# ProdTest.net
KiCad netlist of a schematic drawn in EAGLE
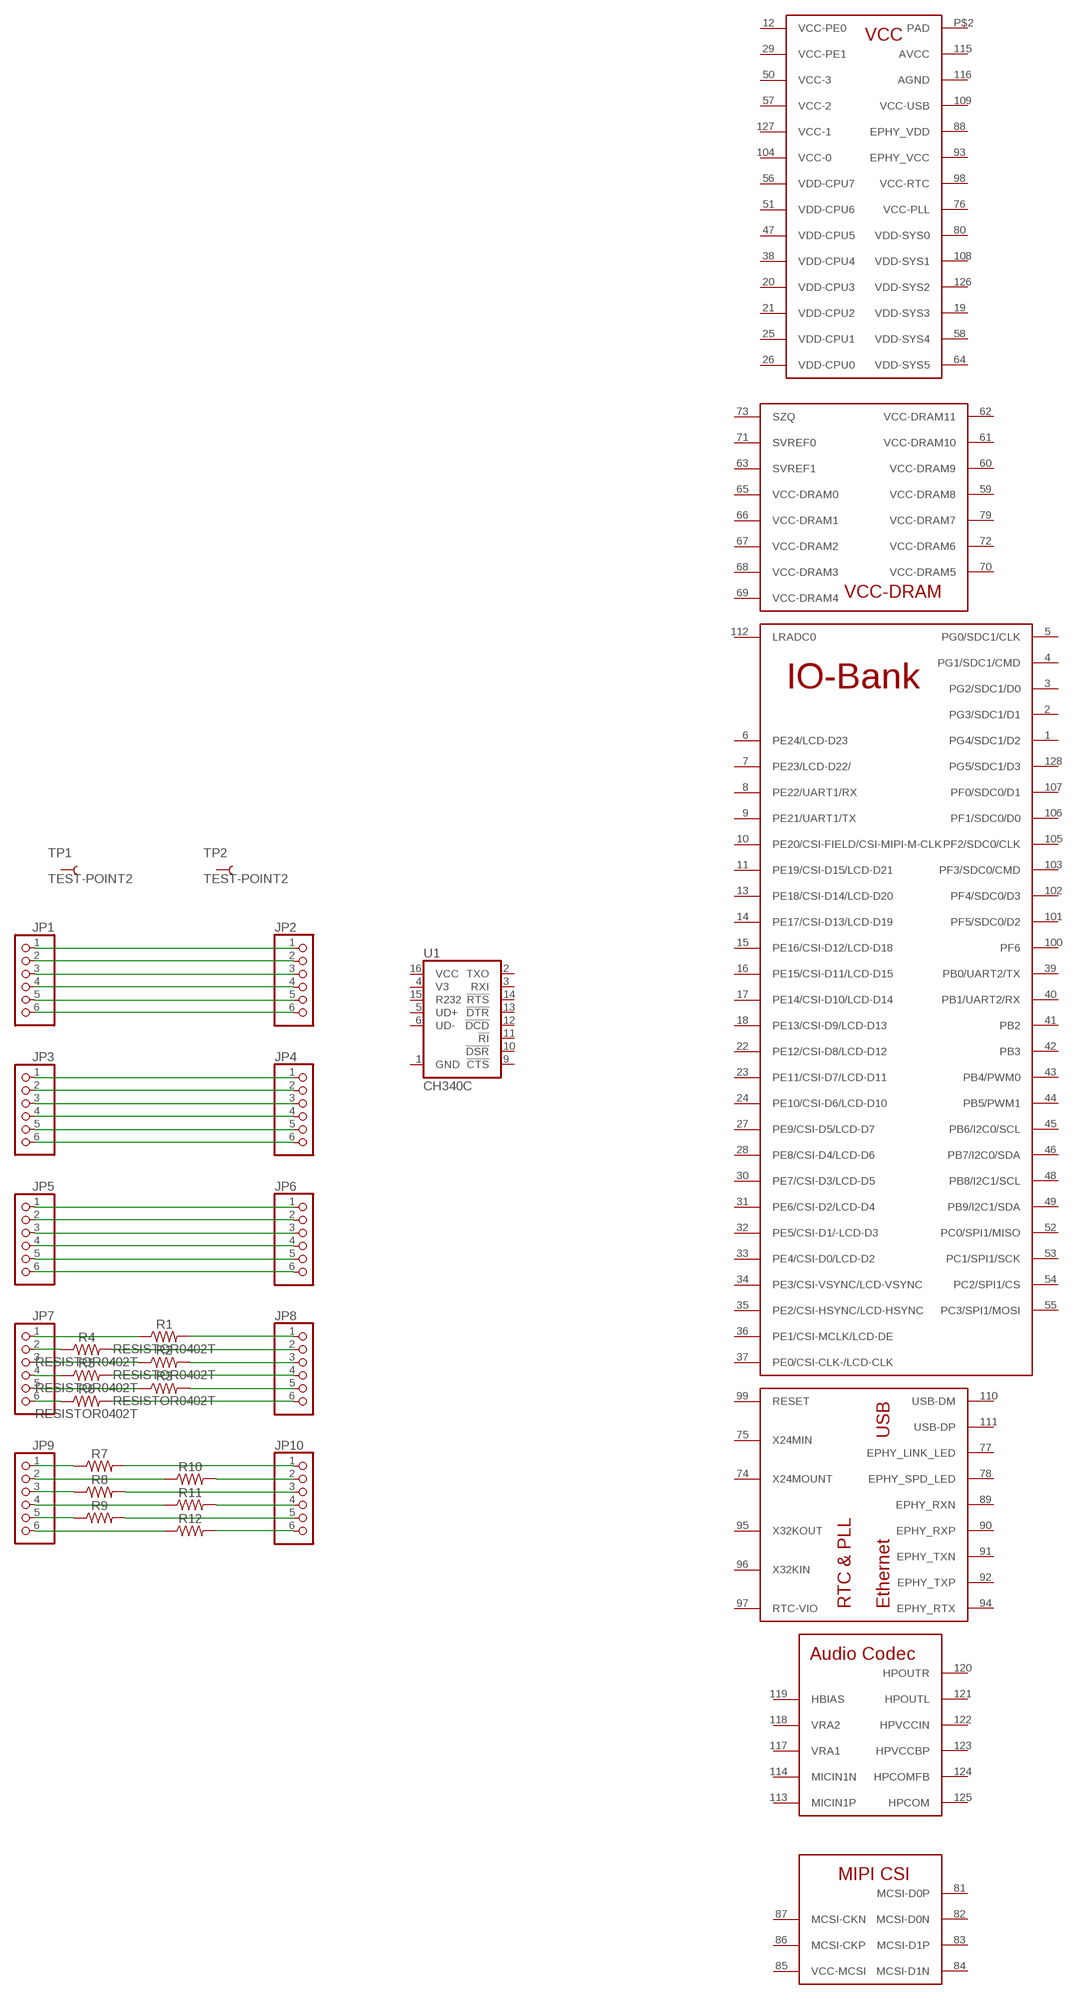
[diagram p0: schematic, sheet 1]

(export (version "E")
  (design (tool "Eeschema 10.0.6"))
  (components
    (comp (ref "JP1")
      (value "PINHD-1X6")
      (footprint "eagle-import:1X06")
      (libsource (lib "eagle-import") (part "PINHD-1X6"))
    )
    (comp (ref "JP2")
      (value "PINHD-1X6")
      (footprint "eagle-import:1X06")
      (libsource (lib "eagle-import") (part "PINHD-1X6"))
    )
    (comp (ref "JP3")
      (value "PINHD-1X6")
      (footprint "eagle-import:1X06")
      (libsource (lib "eagle-import") (part "PINHD-1X6"))
    )
    (comp (ref "JP4")
      (value "PINHD-1X6")
      (footprint "eagle-import:1X06")
      (libsource (lib "eagle-import") (part "PINHD-1X6"))
    )
    (comp (ref "JP5")
      (value "PINHD-1X6")
      (footprint "eagle-import:1X06")
      (libsource (lib "eagle-import") (part "PINHD-1X6"))
    )
    (comp (ref "JP6")
      (value "PINHD-1X6")
      (footprint "eagle-import:1X06")
      (libsource (lib "eagle-import") (part "PINHD-1X6"))
    )
    (comp (ref "JP7")
      (value "PINHD-1X6")
      (footprint "eagle-import:1X06")
      (libsource (lib "eagle-import") (part "PINHD-1X6"))
    )
    (comp (ref "JP8")
      (value "PINHD-1X6")
      (footprint "eagle-import:1X06")
      (libsource (lib "eagle-import") (part "PINHD-1X6"))
    )
    (comp (ref "JP9")
      (value "PINHD-1X6")
      (footprint "eagle-import:1X06")
      (libsource (lib "eagle-import") (part "PINHD-1X6"))
    )
    (comp (ref "JP10")
      (value "PINHD-1X6")
      (footprint "eagle-import:1X06")
      (libsource (lib "eagle-import") (part "PINHD-1X6"))
    )
    (comp (ref "R1")
      (value "RESISTOR0402T")
      (footprint "eagle-import:0402-TIGHT")
      (libsource (lib "eagle-import") (part "RESISTOR0402T"))
    )
    (comp (ref "R2")
      (value "RESISTOR0402T")
      (footprint "eagle-import:0402-TIGHT")
      (libsource (lib "eagle-import") (part "RESISTOR0402T"))
    )
    (comp (ref "R3")
      (value "RESISTOR0402T")
      (footprint "eagle-import:0402-TIGHT")
      (libsource (lib "eagle-import") (part "RESISTOR0402T"))
    )
    (comp (ref "R4")
      (value "RESISTOR0402T")
      (footprint "eagle-import:0402-TIGHT")
      (libsource (lib "eagle-import") (part "RESISTOR0402T"))
    )
    (comp (ref "R5")
      (value "RESISTOR0402T")
      (footprint "eagle-import:0402-TIGHT")
      (libsource (lib "eagle-import") (part "RESISTOR0402T"))
    )
    (comp (ref "R6")
      (value "RESISTOR0402T")
      (footprint "eagle-import:0402-TIGHT")
      (libsource (lib "eagle-import") (part "RESISTOR0402T"))
    )
    (comp (ref "R7")
      (value "RESISTOR0603")
      (footprint "eagle-import:0603")
      (libsource (lib "eagle-import") (part "RESISTOR0603"))
    )
    (comp (ref "R8")
      (value "RESISTOR0603")
      (footprint "eagle-import:0603")
      (libsource (lib "eagle-import") (part "RESISTOR0603"))
    )
    (comp (ref "R9")
      (value "RESISTOR0603")
      (footprint "eagle-import:0603")
      (libsource (lib "eagle-import") (part "RESISTOR0603"))
    )
    (comp (ref "R10")
      (value "RESISTOR0603")
      (footprint "eagle-import:0603")
      (libsource (lib "eagle-import") (part "RESISTOR0603"))
    )
    (comp (ref "R11")
      (value "RESISTOR0603")
      (footprint "eagle-import:0603")
      (libsource (lib "eagle-import") (part "RESISTOR0603"))
    )
    (comp (ref "R12")
      (value "RESISTOR0603")
      (footprint "eagle-import:0603")
      (libsource (lib "eagle-import") (part "RESISTOR0603"))
    )
    (comp (ref "TP1")
      (value "TEST-POINT2")
      (footprint "eagle-import:PAD.02X.02")
      (libsource (lib "eagle-import") (part "TEST-POINT2"))
    )
    (comp (ref "TP2")
      (value "TEST-POINT2")
      (footprint "eagle-import:PAD.02X.02")
      (libsource (lib "eagle-import") (part "TEST-POINT2"))
    )
    (comp (ref "U$1")
      (value "V3S")
      (footprint "eagle-import:QFP-128")
      (libsource (lib "eagle-import") (part "V3S"))
    )
    (comp (ref "U1")
      (value "CH340C")
      (footprint "eagle-import:SO016")
      (libsource (lib "eagle-import") (part "CH340C"))
    )
  )
  (nets
    (net (code "1") (name "Net-(JP1-Pad1)") (class "Default")
      (node (ref "JP1") (pin "1") (pinfunction "1_1") (pintype "passive"))
      (node (ref "JP2") (pin "1") (pinfunction "1_1") (pintype "passive"))
    )
    (net (code "2") (name "Net-(JP1-Pad2)") (class "Default")
      (node (ref "JP1") (pin "2") (pinfunction "2_2") (pintype "passive"))
      (node (ref "JP2") (pin "2") (pinfunction "2_2") (pintype "passive"))
    )
    (net (code "3") (name "Net-(JP1-Pad3)") (class "Default")
      (node (ref "JP1") (pin "3") (pinfunction "3_3") (pintype "passive"))
      (node (ref "JP2") (pin "3") (pinfunction "3_3") (pintype "passive"))
    )
    (net (code "4") (name "Net-(JP1-Pad4)") (class "Default")
      (node (ref "JP1") (pin "4") (pinfunction "4_4") (pintype "passive"))
      (node (ref "JP2") (pin "4") (pinfunction "4_4") (pintype "passive"))
    )
    (net (code "5") (name "Net-(JP1-Pad5)") (class "Default")
      (node (ref "JP1") (pin "5") (pinfunction "5_5") (pintype "passive"))
      (node (ref "JP2") (pin "5") (pinfunction "5_5") (pintype "passive"))
    )
    (net (code "6") (name "Net-(JP1-Pad6)") (class "Default")
      (node (ref "JP1") (pin "6") (pinfunction "6_6") (pintype "passive"))
      (node (ref "JP2") (pin "6") (pinfunction "6_6") (pintype "passive"))
    )
    (net (code "7") (name "Net-(JP3-Pad1)") (class "Default")
      (node (ref "JP3") (pin "1") (pinfunction "1_1") (pintype "passive"))
      (node (ref "JP4") (pin "1") (pinfunction "1_1") (pintype "passive"))
    )
    (net (code "8") (name "Net-(JP3-Pad2)") (class "Default")
      (node (ref "JP3") (pin "2") (pinfunction "2_2") (pintype "passive"))
      (node (ref "JP4") (pin "2") (pinfunction "2_2") (pintype "passive"))
    )
    (net (code "9") (name "Net-(JP3-Pad3)") (class "Default")
      (node (ref "JP3") (pin "3") (pinfunction "3_3") (pintype "passive"))
      (node (ref "JP4") (pin "3") (pinfunction "3_3") (pintype "passive"))
    )
    (net (code "10") (name "Net-(JP3-Pad4)") (class "Default")
      (node (ref "JP3") (pin "4") (pinfunction "4_4") (pintype "passive"))
      (node (ref "JP4") (pin "4") (pinfunction "4_4") (pintype "passive"))
    )
    (net (code "11") (name "Net-(JP3-Pad5)") (class "Default")
      (node (ref "JP3") (pin "5") (pinfunction "5_5") (pintype "passive"))
      (node (ref "JP4") (pin "5") (pinfunction "5_5") (pintype "passive"))
    )
    (net (code "12") (name "Net-(JP3-Pad6)") (class "Default")
      (node (ref "JP3") (pin "6") (pinfunction "6_6") (pintype "passive"))
      (node (ref "JP4") (pin "6") (pinfunction "6_6") (pintype "passive"))
    )
    (net (code "13") (name "Net-(JP5-Pad1)") (class "Default")
      (node (ref "JP5") (pin "1") (pinfunction "1_1") (pintype "passive"))
      (node (ref "JP6") (pin "1") (pinfunction "1_1") (pintype "passive"))
    )
    (net (code "14") (name "Net-(JP5-Pad2)") (class "Default")
      (node (ref "JP5") (pin "2") (pinfunction "2_2") (pintype "passive"))
      (node (ref "JP6") (pin "2") (pinfunction "2_2") (pintype "passive"))
    )
    (net (code "15") (name "Net-(JP5-Pad3)") (class "Default")
      (node (ref "JP5") (pin "3") (pinfunction "3_3") (pintype "passive"))
      (node (ref "JP6") (pin "3") (pinfunction "3_3") (pintype "passive"))
    )
    (net (code "16") (name "Net-(JP5-Pad4)") (class "Default")
      (node (ref "JP5") (pin "4") (pinfunction "4_4") (pintype "passive"))
      (node (ref "JP6") (pin "4") (pinfunction "4_4") (pintype "passive"))
    )
    (net (code "17") (name "Net-(JP5-Pad5)") (class "Default")
      (node (ref "JP5") (pin "5") (pinfunction "5_5") (pintype "passive"))
      (node (ref "JP6") (pin "5") (pinfunction "5_5") (pintype "passive"))
    )
    (net (code "18") (name "Net-(JP5-Pad6)") (class "Default")
      (node (ref "JP5") (pin "6") (pinfunction "6_6") (pintype "passive"))
      (node (ref "JP6") (pin "6") (pinfunction "6_6") (pintype "passive"))
    )
    (net (code "19") (name "Net-(JP7-Pad1)") (class "Default")
      (node (ref "JP7") (pin "1") (pinfunction "1_1") (pintype "passive"))
      (node (ref "R1") (pin "1") (pinfunction "1_1") (pintype "passive"))
    )
    (net (code "20") (name "Net-(JP7-Pad2)") (class "Default")
      (node (ref "JP7") (pin "2") (pinfunction "2_2") (pintype "passive"))
      (node (ref "R4") (pin "1") (pinfunction "1_1") (pintype "passive"))
    )
    (net (code "21") (name "Net-(JP7-Pad3)") (class "Default")
      (node (ref "JP7") (pin "3") (pinfunction "3_3") (pintype "passive"))
      (node (ref "R2") (pin "1") (pinfunction "1_1") (pintype "passive"))
    )
    (net (code "22") (name "Net-(JP7-Pad4)") (class "Default")
      (node (ref "JP7") (pin "4") (pinfunction "4_4") (pintype "passive"))
      (node (ref "R5") (pin "1") (pinfunction "1_1") (pintype "passive"))
    )
    (net (code "23") (name "Net-(JP7-Pad5)") (class "Default")
      (node (ref "JP7") (pin "5") (pinfunction "5_5") (pintype "passive"))
      (node (ref "R3") (pin "1") (pinfunction "1_1") (pintype "passive"))
    )
    (net (code "24") (name "Net-(JP7-Pad6)") (class "Default")
      (node (ref "JP7") (pin "6") (pinfunction "6_6") (pintype "passive"))
      (node (ref "R6") (pin "1") (pinfunction "1_1") (pintype "passive"))
    )
    (net (code "25") (name "Net-(JP8-Pad1)") (class "Default")
      (node (ref "JP8") (pin "1") (pinfunction "1_1") (pintype "passive"))
      (node (ref "R1") (pin "2") (pinfunction "2_2") (pintype "passive"))
    )
    (net (code "26") (name "Net-(JP8-Pad2)") (class "Default")
      (node (ref "JP8") (pin "2") (pinfunction "2_2") (pintype "passive"))
      (node (ref "R4") (pin "2") (pinfunction "2_2") (pintype "passive"))
    )
    (net (code "27") (name "Net-(JP8-Pad3)") (class "Default")
      (node (ref "JP8") (pin "3") (pinfunction "3_3") (pintype "passive"))
      (node (ref "R2") (pin "2") (pinfunction "2_2") (pintype "passive"))
    )
    (net (code "28") (name "Net-(JP8-Pad4)") (class "Default")
      (node (ref "JP8") (pin "4") (pinfunction "4_4") (pintype "passive"))
      (node (ref "R5") (pin "2") (pinfunction "2_2") (pintype "passive"))
    )
    (net (code "29") (name "Net-(JP8-Pad5)") (class "Default")
      (node (ref "JP8") (pin "5") (pinfunction "5_5") (pintype "passive"))
      (node (ref "R3") (pin "2") (pinfunction "2_2") (pintype "passive"))
    )
    (net (code "30") (name "Net-(JP8-Pad6)") (class "Default")
      (node (ref "JP8") (pin "6") (pinfunction "6_6") (pintype "passive"))
      (node (ref "R6") (pin "2") (pinfunction "2_2") (pintype "passive"))
    )
    (net (code "31") (name "Net-(JP9-Pad1)") (class "Default")
      (node (ref "JP9") (pin "1") (pinfunction "1_1") (pintype "passive"))
      (node (ref "R7") (pin "1") (pinfunction "1_1") (pintype "passive"))
    )
    (net (code "32") (name "Net-(JP9-Pad2)") (class "Default")
      (node (ref "JP9") (pin "2") (pinfunction "2_2") (pintype "passive"))
      (node (ref "R10") (pin "1") (pinfunction "1_1") (pintype "passive"))
    )
    (net (code "33") (name "Net-(JP9-Pad3)") (class "Default")
      (node (ref "JP9") (pin "3") (pinfunction "3_3") (pintype "passive"))
      (node (ref "R8") (pin "1") (pinfunction "1_1") (pintype "passive"))
    )
    (net (code "34") (name "Net-(JP9-Pad4)") (class "Default")
      (node (ref "JP9") (pin "4") (pinfunction "4_4") (pintype "passive"))
      (node (ref "R11") (pin "1") (pinfunction "1_1") (pintype "passive"))
    )
    (net (code "35") (name "Net-(JP9-Pad5)") (class "Default")
      (node (ref "JP9") (pin "5") (pinfunction "5_5") (pintype "passive"))
      (node (ref "R9") (pin "1") (pinfunction "1_1") (pintype "passive"))
    )
    (net (code "36") (name "Net-(JP9-Pad6)") (class "Default")
      (node (ref "JP9") (pin "6") (pinfunction "6_6") (pintype "passive"))
      (node (ref "R12") (pin "1") (pinfunction "1_1") (pintype "passive"))
    )
    (net (code "37") (name "Net-(JP10-Pad1)") (class "Default")
      (node (ref "JP10") (pin "1") (pinfunction "1_1") (pintype "passive"))
      (node (ref "R7") (pin "2") (pinfunction "2_2") (pintype "passive"))
    )
    (net (code "38") (name "Net-(JP10-Pad2)") (class "Default")
      (node (ref "JP10") (pin "2") (pinfunction "2_2") (pintype "passive"))
      (node (ref "R10") (pin "2") (pinfunction "2_2") (pintype "passive"))
    )
    (net (code "39") (name "Net-(JP10-Pad3)") (class "Default")
      (node (ref "JP10") (pin "3") (pinfunction "3_3") (pintype "passive"))
      (node (ref "R8") (pin "2") (pinfunction "2_2") (pintype "passive"))
    )
    (net (code "40") (name "Net-(JP10-Pad4)") (class "Default")
      (node (ref "JP10") (pin "4") (pinfunction "4_4") (pintype "passive"))
      (node (ref "R11") (pin "2") (pinfunction "2_2") (pintype "passive"))
    )
    (net (code "41") (name "Net-(JP10-Pad5)") (class "Default")
      (node (ref "JP10") (pin "5") (pinfunction "5_5") (pintype "passive"))
      (node (ref "R9") (pin "2") (pinfunction "2_2") (pintype "passive"))
    )
    (net (code "42") (name "Net-(JP10-Pad6)") (class "Default")
      (node (ref "JP10") (pin "6") (pinfunction "6_6") (pintype "passive"))
      (node (ref "R12") (pin "2") (pinfunction "2_2") (pintype "passive"))
    )
    (net (code "43") (name "unconnected-(TP1-Pad1)") (class "Default")
      (node (ref "TP1") (pin "1") (pinfunction "1_1") (pintype "bidirectional"))
    )
    (net (code "44") (name "unconnected-(TP2-Pad1)") (class "Default")
      (node (ref "TP2") (pin "1") (pinfunction "1_1") (pintype "bidirectional"))
    )
    (net (code "45") (name "unconnected-(U$1-AGND-Pad116)") (class "Default")
      (node (ref "U$1") (pin "116") (pinfunction "AGND_116") (pintype "bidirectional"))
    )
    (net (code "46") (name "unconnected-(U$1-AVCC-Pad115)") (class "Default")
      (node (ref "U$1") (pin "115") (pinfunction "AVCC_115") (pintype "bidirectional"))
    )
    (net (code "47") (name "unconnected-(U$1-EPHY_LINK_LED-Pad77)") (class "Default")
      (node (ref "U$1") (pin "77") (pinfunction "EPHY_LINK_LED_77") (pintype "bidirectional"))
    )
    (net (code "48") (name "unconnected-(U$1-EPHY_RTX-Pad94)") (class "Default")
      (node (ref "U$1") (pin "94") (pinfunction "EPHY_RTX_94") (pintype "bidirectional"))
    )
    (net (code "49") (name "unconnected-(U$1-EPHY_RXN-Pad89)") (class "Default")
      (node (ref "U$1") (pin "89") (pinfunction "EPHY_RXN_89") (pintype "bidirectional"))
    )
    (net (code "50") (name "unconnected-(U$1-EPHY_RXP-Pad90)") (class "Default")
      (node (ref "U$1") (pin "90") (pinfunction "EPHY_RXP_90") (pintype "bidirectional"))
    )
    (net (code "51") (name "unconnected-(U$1-EPHY_SPD_LED-Pad78)") (class "Default")
      (node (ref "U$1") (pin "78") (pinfunction "EPHY_SPD_LED_78") (pintype "bidirectional"))
    )
    (net (code "52") (name "unconnected-(U$1-EPHY_TXN-Pad91)") (class "Default")
      (node (ref "U$1") (pin "91") (pinfunction "EPHY_TXN_91") (pintype "bidirectional"))
    )
    (net (code "53") (name "unconnected-(U$1-EPHY_TXP-Pad92)") (class "Default")
      (node (ref "U$1") (pin "92") (pinfunction "EPHY_TXP_92") (pintype "bidirectional"))
    )
    (net (code "54") (name "unconnected-(U$1-EPHY_VCC-Pad93)") (class "Default")
      (node (ref "U$1") (pin "93") (pinfunction "EPHY_VCC_93") (pintype "bidirectional"))
    )
    (net (code "55") (name "unconnected-(U$1-EPHY_VDD-Pad88)") (class "Default")
      (node (ref "U$1") (pin "88") (pinfunction "EPHY_VDD_88") (pintype "bidirectional"))
    )
    (net (code "56") (name "unconnected-(U$1-HBIAS-Pad119)") (class "Default")
      (node (ref "U$1") (pin "119") (pinfunction "HBIAS_119") (pintype "bidirectional"))
    )
    (net (code "57") (name "unconnected-(U$1-HPCOM-Pad125)") (class "Default")
      (node (ref "U$1") (pin "125") (pinfunction "HPCOM_125") (pintype "bidirectional"))
    )
    (net (code "58") (name "unconnected-(U$1-HPCOMFB-Pad124)") (class "Default")
      (node (ref "U$1") (pin "124") (pinfunction "HPCOMFB_124") (pintype "bidirectional"))
    )
    (net (code "59") (name "unconnected-(U$1-HPOUTL-Pad121)") (class "Default")
      (node (ref "U$1") (pin "121") (pinfunction "HPOUTL_121") (pintype "bidirectional"))
    )
    (net (code "60") (name "unconnected-(U$1-HPOUTR-Pad120)") (class "Default")
      (node (ref "U$1") (pin "120") (pinfunction "HPOUTR_120") (pintype "bidirectional"))
    )
    (net (code "61") (name "unconnected-(U$1-HPVCCBP-Pad123)") (class "Default")
      (node (ref "U$1") (pin "123") (pinfunction "HPVCCBP_123") (pintype "bidirectional"))
    )
    (net (code "62") (name "unconnected-(U$1-HPVCCIN-Pad122)") (class "Default")
      (node (ref "U$1") (pin "122") (pinfunction "HPVCCIN_122") (pintype "bidirectional"))
    )
    (net (code "63") (name "unconnected-(U$1-LRADC0-Pad112)") (class "Default")
      (node (ref "U$1") (pin "112") (pinfunction "LRADC0_112") (pintype "bidirectional"))
    )
    (net (code "64") (name "unconnected-(U$1-MCSI-CKN-Pad87)") (class "Default")
      (node (ref "U$1") (pin "87") (pinfunction "MCSI-CKN_87") (pintype "bidirectional"))
    )
    (net (code "65") (name "unconnected-(U$1-MCSI-CKP-Pad86)") (class "Default")
      (node (ref "U$1") (pin "86") (pinfunction "MCSI-CKP_86") (pintype "bidirectional"))
    )
    (net (code "66") (name "unconnected-(U$1-MCSI-D0N-Pad82)") (class "Default")
      (node (ref "U$1") (pin "82") (pinfunction "MCSI-D0N_82") (pintype "bidirectional"))
    )
    (net (code "67") (name "unconnected-(U$1-MCSI-D0P-Pad81)") (class "Default")
      (node (ref "U$1") (pin "81") (pinfunction "MCSI-D0P_81") (pintype "bidirectional"))
    )
    (net (code "68") (name "unconnected-(U$1-MCSI-D1N-Pad84)") (class "Default")
      (node (ref "U$1") (pin "84") (pinfunction "MCSI-D1N_84") (pintype "bidirectional"))
    )
    (net (code "69") (name "unconnected-(U$1-MCSI-D1P-Pad83)") (class "Default")
      (node (ref "U$1") (pin "83") (pinfunction "MCSI-D1P_83") (pintype "bidirectional"))
    )
    (net (code "70") (name "unconnected-(U$1-MICIN1N-Pad114)") (class "Default")
      (node (ref "U$1") (pin "114") (pinfunction "MICIN1N_114") (pintype "bidirectional"))
    )
    (net (code "71") (name "unconnected-(U$1-MICIN1P-Pad113)") (class "Default")
      (node (ref "U$1") (pin "113") (pinfunction "MICIN1P_113") (pintype "bidirectional"))
    )
    (net (code "72") (name "unconnected-(U$1-PAD-PadP$2)") (class "Default")
      (node (ref "U$1") (pin "P$2") (pinfunction "PAD_P$2") (pintype "bidirectional"))
    )
    (net (code "73") (name "unconnected-(U$1-PB0{slash}UART2{slash}TX-Pad39)") (class "Default")
      (node (ref "U$1") (pin "39") (pinfunction "PB0/UART2/TX_39") (pintype "bidirectional"))
    )
    (net (code "74") (name "unconnected-(U$1-PB1{slash}UART2{slash}RX-Pad40)") (class "Default")
      (node (ref "U$1") (pin "40") (pinfunction "PB1/UART2/RX_40") (pintype "bidirectional"))
    )
    (net (code "75") (name "unconnected-(U$1-PB2-Pad41)") (class "Default")
      (node (ref "U$1") (pin "41") (pinfunction "PB2_41") (pintype "bidirectional"))
    )
    (net (code "76") (name "unconnected-(U$1-PB3-Pad42)") (class "Default")
      (node (ref "U$1") (pin "42") (pinfunction "PB3_42") (pintype "bidirectional"))
    )
    (net (code "77") (name "unconnected-(U$1-PB4{slash}PWM0-Pad43)") (class "Default")
      (node (ref "U$1") (pin "43") (pinfunction "PB4/PWM0_43") (pintype "bidirectional"))
    )
    (net (code "78") (name "unconnected-(U$1-PB5{slash}PWM1-Pad44)") (class "Default")
      (node (ref "U$1") (pin "44") (pinfunction "PB5/PWM1_44") (pintype "bidirectional"))
    )
    (net (code "79") (name "unconnected-(U$1-PB6{slash}I2C0{slash}SCL-Pad45)") (class "Default")
      (node (ref "U$1") (pin "45") (pinfunction "PB6/I2C0/SCL_45") (pintype "bidirectional"))
    )
    (net (code "80") (name "unconnected-(U$1-PB7{slash}I2C0{slash}SDA-Pad46)") (class "Default")
      (node (ref "U$1") (pin "46") (pinfunction "PB7/I2C0/SDA_46") (pintype "bidirectional"))
    )
    (net (code "81") (name "unconnected-(U$1-PB8{slash}I2C1{slash}SCL-Pad48)") (class "Default")
      (node (ref "U$1") (pin "48") (pinfunction "PB8/I2C1/SCL_48") (pintype "bidirectional"))
    )
    (net (code "82") (name "unconnected-(U$1-PB9{slash}I2C1{slash}SDA-Pad49)") (class "Default")
      (node (ref "U$1") (pin "49") (pinfunction "PB9/I2C1/SDA_49") (pintype "bidirectional"))
    )
    (net (code "83") (name "unconnected-(U$1-PC0{slash}SPI1{slash}MISO-Pad52)") (class "Default")
      (node (ref "U$1") (pin "52") (pinfunction "PC0/SPI1/MISO_52") (pintype "bidirectional"))
    )
    (net (code "84") (name "unconnected-(U$1-PC1{slash}SPI1{slash}SCK-Pad53)") (class "Default")
      (node (ref "U$1") (pin "53") (pinfunction "PC1/SPI1/SCK_53") (pintype "bidirectional"))
    )
    (net (code "85") (name "unconnected-(U$1-PC2{slash}SPI1{slash}CS-Pad54)") (class "Default")
      (node (ref "U$1") (pin "54") (pinfunction "PC2/SPI1/CS_54") (pintype "bidirectional"))
    )
    (net (code "86") (name "unconnected-(U$1-PC3{slash}SPI1{slash}MOSI-Pad55)") (class "Default")
      (node (ref "U$1") (pin "55") (pinfunction "PC3/SPI1/MOSI_55") (pintype "bidirectional"))
    )
    (net (code "87") (name "unconnected-(U$1-PE0{slash}CSI-CLK-{slash}LCD-CLK-Pad37)") (class "Default")
      (node (ref "U$1") (pin "37") (pinfunction "PE0/CSI-CLK-/LCD-CLK_37") (pintype "bidirectional"))
    )
    (net (code "88") (name "unconnected-(U$1-PE1{slash}CSI-MCLK{slash}LCD-DE-Pad36)") (class "Default")
      (node (ref "U$1") (pin "36") (pinfunction "PE1/CSI-MCLK/LCD-DE_36") (pintype "bidirectional"))
    )
    (net (code "89") (name "unconnected-(U$1-PE2{slash}CSI-HSYNC{slash}LCD-HSYNC-Pad35)") (class "Default")
      (node (ref "U$1") (pin "35") (pinfunction "PE2/CSI-HSYNC/LCD-HSYNC_35") (pintype "bidirectional"))
    )
    (net (code "90") (name "unconnected-(U$1-PE3{slash}CSI-VSYNC{slash}LCD-VSYNC-Pad34)") (class "Default")
      (node (ref "U$1") (pin "34") (pinfunction "PE3/CSI-VSYNC/LCD-VSYNC_34") (pintype "bidirectional"))
    )
    (net (code "91") (name "unconnected-(U$1-PE4{slash}CSI-D0{slash}LCD-D2-Pad33)") (class "Default")
      (node (ref "U$1") (pin "33") (pinfunction "PE4/CSI-D0/LCD-D2_33") (pintype "bidirectional"))
    )
    (net (code "92") (name "unconnected-(U$1-PE5{slash}CSI-D1{slash}-LCD-D3-Pad32)") (class "Default")
      (node (ref "U$1") (pin "32") (pinfunction "PE5/CSI-D1/-LCD-D3_32") (pintype "bidirectional"))
    )
    (net (code "93") (name "unconnected-(U$1-PE6{slash}CSI-D2{slash}LCD-D4-Pad31)") (class "Default")
      (node (ref "U$1") (pin "31") (pinfunction "PE6/CSI-D2/LCD-D4_31") (pintype "bidirectional"))
    )
    (net (code "94") (name "unconnected-(U$1-PE7{slash}CSI-D3{slash}LCD-D5-Pad30)") (class "Default")
      (node (ref "U$1") (pin "30") (pinfunction "PE7/CSI-D3/LCD-D5_30") (pintype "bidirectional"))
    )
    (net (code "95") (name "unconnected-(U$1-PE8{slash}CSI-D4{slash}LCD-D6-Pad28)") (class "Default")
      (node (ref "U$1") (pin "28") (pinfunction "PE8/CSI-D4/LCD-D6_28") (pintype "bidirectional"))
    )
    (net (code "96") (name "unconnected-(U$1-PE9{slash}CSI-D5{slash}LCD-D7-Pad27)") (class "Default")
      (node (ref "U$1") (pin "27") (pinfunction "PE9/CSI-D5/LCD-D7_27") (pintype "bidirectional"))
    )
    (net (code "97") (name "unconnected-(U$1-PE10{slash}CSI-D6{slash}LCD-D10-Pad24)") (class "Default")
      (node (ref "U$1") (pin "24") (pinfunction "PE10/CSI-D6/LCD-D10_24") (pintype "bidirectional"))
    )
    (net (code "98") (name "unconnected-(U$1-PE11{slash}CSI-D7{slash}LCD-D11-Pad23)") (class "Default")
      (node (ref "U$1") (pin "23") (pinfunction "PE11/CSI-D7/LCD-D11_23") (pintype "bidirectional"))
    )
    (net (code "99") (name "unconnected-(U$1-PE12{slash}CSI-D8{slash}LCD-D12-Pad22)") (class "Default")
      (node (ref "U$1") (pin "22") (pinfunction "PE12/CSI-D8/LCD-D12_22") (pintype "bidirectional"))
    )
    (net (code "100") (name "unconnected-(U$1-PE13{slash}CSI-D9{slash}LCD-D13-Pad18)") (class "Default")
      (node (ref "U$1") (pin "18") (pinfunction "PE13/CSI-D9/LCD-D13_18") (pintype "bidirectional"))
    )
    (net (code "101") (name "unconnected-(U$1-PE14{slash}CSI-D10{slash}LCD-D14-Pad17)") (class "Default")
      (node (ref "U$1") (pin "17") (pinfunction "PE14/CSI-D10/LCD-D14_17") (pintype "bidirectional"))
    )
    (net (code "102") (name "unconnected-(U$1-PE15{slash}CSI-D11{slash}LCD-D15-Pad16)") (class "Default")
      (node (ref "U$1") (pin "16") (pinfunction "PE15/CSI-D11/LCD-D15_16") (pintype "bidirectional"))
    )
    (net (code "103") (name "unconnected-(U$1-PE16{slash}CSI-D12{slash}LCD-D18-Pad15)") (class "Default")
      (node (ref "U$1") (pin "15") (pinfunction "PE16/CSI-D12/LCD-D18_15") (pintype "bidirectional"))
    )
    (net (code "104") (name "unconnected-(U$1-PE17{slash}CSI-D13{slash}LCD-D19-Pad14)") (class "Default")
      (node (ref "U$1") (pin "14") (pinfunction "PE17/CSI-D13/LCD-D19_14") (pintype "bidirectional"))
    )
    (net (code "105") (name "unconnected-(U$1-PE18{slash}CSI-D14{slash}LCD-D20-Pad13)") (class "Default")
      (node (ref "U$1") (pin "13") (pinfunction "PE18/CSI-D14/LCD-D20_13") (pintype "bidirectional"))
    )
    (net (code "106") (name "unconnected-(U$1-PE19{slash}CSI-D15{slash}LCD-D21-Pad11)") (class "Default")
      (node (ref "U$1") (pin "11") (pinfunction "PE19/CSI-D15/LCD-D21_11") (pintype "bidirectional"))
    )
    (net (code "107") (name "unconnected-(U$1-PE20{slash}CSI-FIELD{slash}CSI-MIPI-M-CLK-Pad10)") (class "Default")
      (node (ref "U$1") (pin "10") (pinfunction "PE20/CSI-FIELD/CSI-MIPI-M-CLK_10") (pintype "bidirectional"))
    )
    (net (code "108") (name "unconnected-(U$1-PE21{slash}UART1{slash}TX-Pad9)") (class "Default")
      (node (ref "U$1") (pin "9") (pinfunction "PE21/UART1/TX_9") (pintype "bidirectional"))
    )
    (net (code "109") (name "unconnected-(U$1-PE22{slash}UART1{slash}RX-Pad8)") (class "Default")
      (node (ref "U$1") (pin "8") (pinfunction "PE22/UART1/RX_8") (pintype "bidirectional"))
    )
    (net (code "110") (name "unconnected-(U$1-PE23{slash}LCD-D22{slash}-Pad7)") (class "Default")
      (node (ref "U$1") (pin "7") (pinfunction "PE23/LCD-D22/_7") (pintype "bidirectional"))
    )
    (net (code "111") (name "unconnected-(U$1-PE24{slash}LCD-D23-Pad6)") (class "Default")
      (node (ref "U$1") (pin "6") (pinfunction "PE24/LCD-D23_6") (pintype "bidirectional"))
    )
    (net (code "112") (name "unconnected-(U$1-PF0{slash}SDC0{slash}D1-Pad107)") (class "Default")
      (node (ref "U$1") (pin "107") (pinfunction "PF0/SDC0/D1_107") (pintype "bidirectional"))
    )
    (net (code "113") (name "unconnected-(U$1-PF1{slash}SDC0{slash}D0-Pad106)") (class "Default")
      (node (ref "U$1") (pin "106") (pinfunction "PF1/SDC0/D0_106") (pintype "bidirectional"))
    )
    (net (code "114") (name "unconnected-(U$1-PF2{slash}SDC0{slash}CLK-Pad105)") (class "Default")
      (node (ref "U$1") (pin "105") (pinfunction "PF2/SDC0/CLK_105") (pintype "bidirectional"))
    )
    (net (code "115") (name "unconnected-(U$1-PF3{slash}SDC0{slash}CMD-Pad103)") (class "Default")
      (node (ref "U$1") (pin "103") (pinfunction "PF3/SDC0/CMD_103") (pintype "bidirectional"))
    )
    (net (code "116") (name "unconnected-(U$1-PF4{slash}SDC0{slash}D3-Pad102)") (class "Default")
      (node (ref "U$1") (pin "102") (pinfunction "PF4/SDC0/D3_102") (pintype "bidirectional"))
    )
    (net (code "117") (name "unconnected-(U$1-PF5{slash}SDC0{slash}D2-Pad101)") (class "Default")
      (node (ref "U$1") (pin "101") (pinfunction "PF5/SDC0/D2_101") (pintype "bidirectional"))
    )
    (net (code "118") (name "unconnected-(U$1-PF6-Pad100)") (class "Default")
      (node (ref "U$1") (pin "100") (pinfunction "PF6_100") (pintype "bidirectional"))
    )
    (net (code "119") (name "unconnected-(U$1-PG0{slash}SDC1{slash}CLK-Pad5)") (class "Default")
      (node (ref "U$1") (pin "5") (pinfunction "PG0/SDC1/CLK_5") (pintype "bidirectional"))
    )
    (net (code "120") (name "unconnected-(U$1-PG1{slash}SDC1{slash}CMD-Pad4)") (class "Default")
      (node (ref "U$1") (pin "4") (pinfunction "PG1/SDC1/CMD_4") (pintype "bidirectional"))
    )
    (net (code "121") (name "unconnected-(U$1-PG2{slash}SDC1{slash}D0-Pad3)") (class "Default")
      (node (ref "U$1") (pin "3") (pinfunction "PG2/SDC1/D0_3") (pintype "bidirectional"))
    )
    (net (code "122") (name "unconnected-(U$1-PG3{slash}SDC1{slash}D1-Pad2)") (class "Default")
      (node (ref "U$1") (pin "2") (pinfunction "PG3/SDC1/D1_2") (pintype "bidirectional"))
    )
    (net (code "123") (name "unconnected-(U$1-PG4{slash}SDC1{slash}D2-Pad1)") (class "Default")
      (node (ref "U$1") (pin "1") (pinfunction "PG4/SDC1/D2_1") (pintype "bidirectional"))
    )
    (net (code "124") (name "unconnected-(U$1-PG5{slash}SDC1{slash}D3-Pad128)") (class "Default")
      (node (ref "U$1") (pin "128") (pinfunction "PG5/SDC1/D3_128") (pintype "bidirectional"))
    )
    (net (code "125") (name "unconnected-(U$1-RESET-Pad99)") (class "Default")
      (node (ref "U$1") (pin "99") (pinfunction "RESET_99") (pintype "bidirectional"))
    )
    (net (code "126") (name "unconnected-(U$1-RTC-VIO-Pad97)") (class "Default")
      (node (ref "U$1") (pin "97") (pinfunction "RTC-VIO_97") (pintype "bidirectional"))
    )
    (net (code "127") (name "unconnected-(U$1-SVREF0-Pad71)") (class "Default")
      (node (ref "U$1") (pin "71") (pinfunction "SVREF0_71") (pintype "bidirectional"))
    )
    (net (code "128") (name "unconnected-(U$1-SVREF1-Pad63)") (class "Default")
      (node (ref "U$1") (pin "63") (pinfunction "SVREF1_63") (pintype "bidirectional"))
    )
    (net (code "129") (name "unconnected-(U$1-SZQ-Pad73)") (class "Default")
      (node (ref "U$1") (pin "73") (pinfunction "SZQ_73") (pintype "bidirectional"))
    )
    (net (code "130") (name "unconnected-(U$1-USB-DM-Pad110)") (class "Default")
      (node (ref "U$1") (pin "110") (pinfunction "USB-DM_110") (pintype "bidirectional"))
    )
    (net (code "131") (name "unconnected-(U$1-USB-DP-Pad111)") (class "Default")
      (node (ref "U$1") (pin "111") (pinfunction "USB-DP_111") (pintype "bidirectional"))
    )
    (net (code "132") (name "unconnected-(U$1-VCC-0-Pad104)") (class "Default")
      (node (ref "U$1") (pin "104") (pinfunction "VCC-0_104") (pintype "bidirectional"))
    )
    (net (code "133") (name "unconnected-(U$1-VCC-1-Pad127)") (class "Default")
      (node (ref "U$1") (pin "127") (pinfunction "VCC-1_127") (pintype "bidirectional"))
    )
    (net (code "134") (name "unconnected-(U$1-VCC-2-Pad57)") (class "Default")
      (node (ref "U$1") (pin "57") (pinfunction "VCC-2_57") (pintype "bidirectional"))
    )
    (net (code "135") (name "unconnected-(U$1-VCC-3-Pad50)") (class "Default")
      (node (ref "U$1") (pin "50") (pinfunction "VCC-3_50") (pintype "bidirectional"))
    )
    (net (code "136") (name "unconnected-(U$1-VCC-DRAM0-Pad65)") (class "Default")
      (node (ref "U$1") (pin "65") (pinfunction "VCC-DRAM0_65") (pintype "bidirectional"))
    )
    (net (code "137") (name "unconnected-(U$1-VCC-DRAM1-Pad66)") (class "Default")
      (node (ref "U$1") (pin "66") (pinfunction "VCC-DRAM1_66") (pintype "bidirectional"))
    )
    (net (code "138") (name "unconnected-(U$1-VCC-DRAM2-Pad67)") (class "Default")
      (node (ref "U$1") (pin "67") (pinfunction "VCC-DRAM2_67") (pintype "bidirectional"))
    )
    (net (code "139") (name "unconnected-(U$1-VCC-DRAM3-Pad68)") (class "Default")
      (node (ref "U$1") (pin "68") (pinfunction "VCC-DRAM3_68") (pintype "bidirectional"))
    )
    (net (code "140") (name "unconnected-(U$1-VCC-DRAM4-Pad69)") (class "Default")
      (node (ref "U$1") (pin "69") (pinfunction "VCC-DRAM4_69") (pintype "bidirectional"))
    )
    (net (code "141") (name "unconnected-(U$1-VCC-DRAM5-Pad70)") (class "Default")
      (node (ref "U$1") (pin "70") (pinfunction "VCC-DRAM5_70") (pintype "bidirectional"))
    )
    (net (code "142") (name "unconnected-(U$1-VCC-DRAM6-Pad72)") (class "Default")
      (node (ref "U$1") (pin "72") (pinfunction "VCC-DRAM6_72") (pintype "bidirectional"))
    )
    (net (code "143") (name "unconnected-(U$1-VCC-DRAM7-Pad79)") (class "Default")
      (node (ref "U$1") (pin "79") (pinfunction "VCC-DRAM7_79") (pintype "bidirectional"))
    )
    (net (code "144") (name "unconnected-(U$1-VCC-DRAM8-Pad59)") (class "Default")
      (node (ref "U$1") (pin "59") (pinfunction "VCC-DRAM8_59") (pintype "bidirectional"))
    )
    (net (code "145") (name "unconnected-(U$1-VCC-DRAM9-Pad60)") (class "Default")
      (node (ref "U$1") (pin "60") (pinfunction "VCC-DRAM9_60") (pintype "bidirectional"))
    )
    (net (code "146") (name "unconnected-(U$1-VCC-DRAM10-Pad61)") (class "Default")
      (node (ref "U$1") (pin "61") (pinfunction "VCC-DRAM10_61") (pintype "bidirectional"))
    )
    (net (code "147") (name "unconnected-(U$1-VCC-DRAM11-Pad62)") (class "Default")
      (node (ref "U$1") (pin "62") (pinfunction "VCC-DRAM11_62") (pintype "bidirectional"))
    )
    (net (code "148") (name "unconnected-(U$1-VCC-MCSI-Pad85)") (class "Default")
      (node (ref "U$1") (pin "85") (pinfunction "VCC-MCSI_85") (pintype "bidirectional"))
    )
    (net (code "149") (name "unconnected-(U$1-VCC-PE0-Pad12)") (class "Default")
      (node (ref "U$1") (pin "12") (pinfunction "VCC-PE0_12") (pintype "bidirectional"))
    )
    (net (code "150") (name "unconnected-(U$1-VCC-PE1-Pad29)") (class "Default")
      (node (ref "U$1") (pin "29") (pinfunction "VCC-PE1_29") (pintype "bidirectional"))
    )
    (net (code "151") (name "unconnected-(U$1-VCC-PLL-Pad76)") (class "Default")
      (node (ref "U$1") (pin "76") (pinfunction "VCC-PLL_76") (pintype "bidirectional"))
    )
    (net (code "152") (name "unconnected-(U$1-VCC-RTC-Pad98)") (class "Default")
      (node (ref "U$1") (pin "98") (pinfunction "VCC-RTC_98") (pintype "bidirectional"))
    )
    (net (code "153") (name "unconnected-(U$1-VCC-USB-Pad109)") (class "Default")
      (node (ref "U$1") (pin "109") (pinfunction "VCC-USB_109") (pintype "bidirectional"))
    )
    (net (code "154") (name "unconnected-(U$1-VDD-CPU0-Pad26)") (class "Default")
      (node (ref "U$1") (pin "26") (pinfunction "VDD-CPU0_26") (pintype "bidirectional"))
    )
    (net (code "155") (name "unconnected-(U$1-VDD-CPU1-Pad25)") (class "Default")
      (node (ref "U$1") (pin "25") (pinfunction "VDD-CPU1_25") (pintype "bidirectional"))
    )
    (net (code "156") (name "unconnected-(U$1-VDD-CPU2-Pad21)") (class "Default")
      (node (ref "U$1") (pin "21") (pinfunction "VDD-CPU2_21") (pintype "bidirectional"))
    )
    (net (code "157") (name "unconnected-(U$1-VDD-CPU3-Pad20)") (class "Default")
      (node (ref "U$1") (pin "20") (pinfunction "VDD-CPU3_20") (pintype "bidirectional"))
    )
    (net (code "158") (name "unconnected-(U$1-VDD-CPU4-Pad38)") (class "Default")
      (node (ref "U$1") (pin "38") (pinfunction "VDD-CPU4_38") (pintype "bidirectional"))
    )
    (net (code "159") (name "unconnected-(U$1-VDD-CPU5-Pad47)") (class "Default")
      (node (ref "U$1") (pin "47") (pinfunction "VDD-CPU5_47") (pintype "bidirectional"))
    )
    (net (code "160") (name "unconnected-(U$1-VDD-CPU6-Pad51)") (class "Default")
      (node (ref "U$1") (pin "51") (pinfunction "VDD-CPU6_51") (pintype "bidirectional"))
    )
    (net (code "161") (name "unconnected-(U$1-VDD-CPU7-Pad56)") (class "Default")
      (node (ref "U$1") (pin "56") (pinfunction "VDD-CPU7_56") (pintype "bidirectional"))
    )
    (net (code "162") (name "unconnected-(U$1-VDD-SYS0-Pad80)") (class "Default")
      (node (ref "U$1") (pin "80") (pinfunction "VDD-SYS0_80") (pintype "bidirectional"))
    )
    (net (code "163") (name "unconnected-(U$1-VDD-SYS1-Pad108)") (class "Default")
      (node (ref "U$1") (pin "108") (pinfunction "VDD-SYS1_108") (pintype "bidirectional"))
    )
    (net (code "164") (name "unconnected-(U$1-VDD-SYS2-Pad126)") (class "Default")
      (node (ref "U$1") (pin "126") (pinfunction "VDD-SYS2_126") (pintype "bidirectional"))
    )
    (net (code "165") (name "unconnected-(U$1-VDD-SYS3-Pad19)") (class "Default")
      (node (ref "U$1") (pin "19") (pinfunction "VDD-SYS3_19") (pintype "bidirectional"))
    )
    (net (code "166") (name "unconnected-(U$1-VDD-SYS4-Pad58)") (class "Default")
      (node (ref "U$1") (pin "58") (pinfunction "VDD-SYS4_58") (pintype "bidirectional"))
    )
    (net (code "167") (name "unconnected-(U$1-VDD-SYS5-Pad64)") (class "Default")
      (node (ref "U$1") (pin "64") (pinfunction "VDD-SYS5_64") (pintype "bidirectional"))
    )
    (net (code "168") (name "unconnected-(U$1-VRA1-Pad117)") (class "Default")
      (node (ref "U$1") (pin "117") (pinfunction "VRA1_117") (pintype "bidirectional"))
    )
    (net (code "169") (name "unconnected-(U$1-VRA2-Pad118)") (class "Default")
      (node (ref "U$1") (pin "118") (pinfunction "VRA2_118") (pintype "bidirectional"))
    )
    (net (code "170") (name "unconnected-(U$1-X24MIN-Pad75)") (class "Default")
      (node (ref "U$1") (pin "75") (pinfunction "X24MIN_75") (pintype "bidirectional"))
    )
    (net (code "171") (name "unconnected-(U$1-X24MOUNT-Pad74)") (class "Default")
      (node (ref "U$1") (pin "74") (pinfunction "X24MOUNT_74") (pintype "bidirectional"))
    )
    (net (code "172") (name "unconnected-(U$1-X32KIN-Pad96)") (class "Default")
      (node (ref "U$1") (pin "96") (pinfunction "X32KIN_96") (pintype "bidirectional"))
    )
    (net (code "173") (name "unconnected-(U$1-X32KOUT-Pad95)") (class "Default")
      (node (ref "U$1") (pin "95") (pinfunction "X32KOUT_95") (pintype "bidirectional"))
    )
    (net (code "174") (name "unconnected-(U1-GND-Pad1)") (class "Default")
      (node (ref "U1") (pin "1") (pinfunction "GND_1") (pintype "bidirectional"))
    )
    (net (code "175") (name "unconnected-(U1-R232-Pad15)") (class "Default")
      (node (ref "U1") (pin "15") (pinfunction "R232_15") (pintype "bidirectional"))
    )
    (net (code "176") (name "unconnected-(U1-RXI-Pad3)") (class "Default")
      (node (ref "U1") (pin "3") (pinfunction "RXI_3") (pintype "bidirectional"))
    )
    (net (code "177") (name "unconnected-(U1-TXO-Pad2)") (class "Default")
      (node (ref "U1") (pin "2") (pinfunction "TXO_2") (pintype "bidirectional"))
    )
    (net (code "178") (name "unconnected-(U1-UD+-Pad5)") (class "Default")
      (node (ref "U1") (pin "5") (pinfunction "UD+_5") (pintype "bidirectional"))
    )
    (net (code "179") (name "unconnected-(U1-UD--Pad6)") (class "Default")
      (node (ref "U1") (pin "6") (pinfunction "UD-_6") (pintype "bidirectional"))
    )
    (net (code "180") (name "unconnected-(U1-V3-Pad4)") (class "Default")
      (node (ref "U1") (pin "4") (pinfunction "V3_4") (pintype "bidirectional"))
    )
    (net (code "181") (name "unconnected-(U1-VCC-Pad16)") (class "Default")
      (node (ref "U1") (pin "16") (pinfunction "VCC_16") (pintype "bidirectional"))
    )
    (net (code "182") (name "unconnected-(U1-~{CTS}-Pad9)") (class "Default")
      (node (ref "U1") (pin "9") (pinfunction "~{CTS}_9") (pintype "bidirectional"))
    )
    (net (code "183") (name "unconnected-(U1-~{DCD}-Pad12)") (class "Default")
      (node (ref "U1") (pin "12") (pinfunction "~{DCD}_12") (pintype "bidirectional"))
    )
    (net (code "184") (name "unconnected-(U1-~{DSR}-Pad10)") (class "Default")
      (node (ref "U1") (pin "10") (pinfunction "~{DSR}_10") (pintype "bidirectional"))
    )
    (net (code "185") (name "unconnected-(U1-~{DTR}-Pad13)") (class "Default")
      (node (ref "U1") (pin "13") (pinfunction "~{DTR}_13") (pintype "bidirectional"))
    )
    (net (code "186") (name "unconnected-(U1-~{RI}-Pad11)") (class "Default")
      (node (ref "U1") (pin "11") (pinfunction "~{RI}_11") (pintype "bidirectional"))
    )
    (net (code "187") (name "unconnected-(U1-~{RTS}-Pad14)") (class "Default")
      (node (ref "U1") (pin "14") (pinfunction "~{RTS}_14") (pintype "bidirectional"))
    )
  )
)
